# MCU.net
KiCad netlist of a schematic drawn in Altium Designer
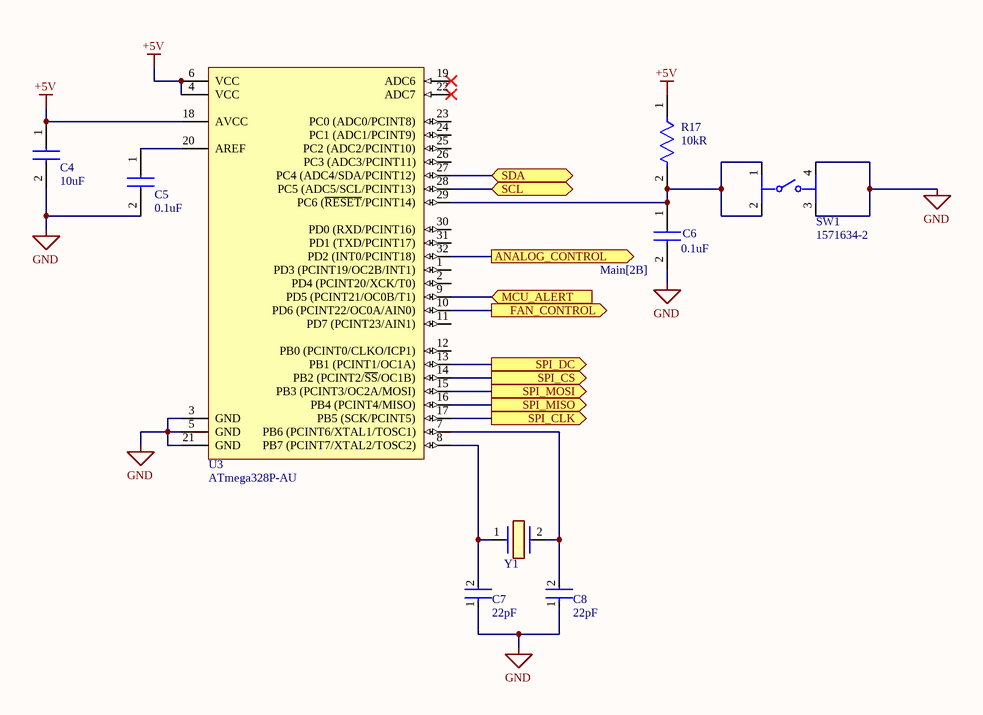
[diagram p0: MCU.SchDoc]

(export (version "E")
  (design (tool "Eeschema 10.0.6"))
  (components
    (comp (ref "C4")
      (value "CL31A106MAHNNNE")
      (footprint "SamacSys:CAPC3216X180N")
      (description "CAP CER 10UF 25V X5R 1206 CL31A106MAHNNNE")
      (fields (field (name "MOUSER PART NUMBER") "187-CL31A106MAHNNNE") (field (name "CAPACITANCE") "10uF"))
      (libsource (lib "SamacSys") (part "CL31A106MAHNNNE"))
    )
    (comp (ref "C5")
      (value "CL31B104KBCNNNC")
      (footprint "SamacSys:CAPC3216X100N")
      (description "CAP CER 0.1UF 50V X7R 1206")
      (fields (field (name "MOUSER PART NUMBER") "187-CL31B104KBCNNNC") (field (name "CAPACITANCE") "0.1uF"))
      (libsource (lib "SamacSys") (part "CL31B104KBCNNNC"))
    )
    (comp (ref "C6")
      (value "CL31B104KBCNNNC")
      (footprint "SamacSys:CAPC3216X100N")
      (description "CAP CER 0.1UF 50V X7R 1206")
      (fields (field (name "MOUSER PART NUMBER") "187-CL31B104KBCNNNC") (field (name "CAPACITANCE") "0.1uF"))
      (libsource (lib "SamacSys") (part "CL31B104KBCNNNC"))
    )
    (comp (ref "C7")
      (value "CL31C220JBCNNNC")
      (footprint "FP-CL31-IPC_A")
      (description "Cap Ceramic 22pF 50V C0G ±5% SMD 1206 +125°C Embossed T/R")
      (fields
        (field (name "VOLTAGE") "50V")
        (field (name "TOLERANCE") "5%")
        (field (name "CAPACITANCE") "22pF")
      )
      (libsource (lib "Altium Content Vault") (part "b4654b650e69147ec39a6b967a45e02"))
    )
    (comp (ref "C8")
      (value "CL31C220JBCNNNC")
      (footprint "FP-CL31-IPC_A")
      (description "Cap Ceramic 22pF 50V C0G ±5% SMD 1206 +125°C Embossed T/R")
      (fields
        (field (name "VOLTAGE") "50V")
        (field (name "TOLERANCE") "5%")
        (field (name "CAPACITANCE") "22pF")
      )
      (libsource (lib "Altium Content Vault") (part "b4654b650e69147ec39a6b967a45e02"))
    )
    (comp (ref "R17")
      (value "RMCF1206FT10K0")
      (footprint "FP-RMCF1206-IPC_B")
      (description "10kΩ ±1% 0.25W 1206 Thick Film Chip Resistor AEC-Q200 compliant RMCF1206FT10K0")
      (fields (field (name "RESISTANCE") "10kR") (field (name "TOLERANCE") "1%"))
      (libsource (lib "Altium Content Vault") (part "1029c3af85768c4190bb7ad29bc67b5"))
    )
    (comp (ref "SW1")
      (value "1571634-2")
      (footprint "FP-1571634-2-MFG")
      (description "SWITCH TACTILE SPST-NO 0.05A 24V")
      (libsource (lib "Altium Content Vault") (part "512b1658425e80dc09bd29e095ee4d3"))
    )
    (comp (ref "U3")
      (value "ATmega328P-AU")
      (footprint "32A_M")
      (libsource (lib "Altium Content Vault") (part "MC-8B-ATM48-SQ32"))
    )
    (comp (ref "Y1")
      (value "ECS-160-20-3X-TR")
      (footprint "SamacSys:ECS160203XTR")
      (description "Crystal or Oscillator")
      (fields (field (name "MOUSER PART NUMBER") "520-160-20-3XT"))
      (libsource (lib "SamacSys") (part "ECS-160-20-3X-TR"))
    )
  )
  (nets
    (net (code "1") (name "+5V") (class "Default")
      (node (ref "C4") (pin "1") (pinfunction "1_1") (pintype "passive"))
      (node (ref "R17") (pin "1") (pinfunction "1_1") (pintype "passive"))
      (node (ref "U3") (pin "18") (pinfunction "AVCC_18") (pintype "power_in"))
      (node (ref "U3") (pin "4") (pinfunction "VCC_4") (pintype "power_in"))
      (node (ref "U3") (pin "6") (pinfunction "VCC_6") (pintype "power_in"))
    )
    (net (code "2") (name "/ANALOG_CONTROL") (class "Default")
      (node (ref "U3") (pin "32") (pinfunction "PD2_(INT0/PCINT18)_32") (pintype "bidirectional"))
    )
    (net (code "3") (name "/FAN_CONTROL") (class "Default")
      (node (ref "U3") (pin "10") (pinfunction "PD6_(PCINT22/OC0A/AIN0)_10") (pintype "bidirectional"))
    )
    (net (code "4") (name "/MCU_ALERT") (class "Default")
      (node (ref "U3") (pin "9") (pinfunction "PD5_(PCINT21/OC0B/T1)_9") (pintype "bidirectional"))
    )
    (net (code "5") (name "/SCL") (class "Default")
      (node (ref "U3") (pin "28") (pinfunction "PC5_(ADC5/SCL/PCINT13)_28") (pintype "bidirectional"))
    )
    (net (code "6") (name "/SDA") (class "Default")
      (node (ref "U3") (pin "27") (pinfunction "PC4_(ADC4/SDA/PCINT12)_27") (pintype "bidirectional"))
    )
    (net (code "7") (name "/SPI_CLK") (class "Default")
      (node (ref "U3") (pin "17") (pinfunction "PB5_(SCK/PCINT5)_17") (pintype "bidirectional"))
    )
    (net (code "8") (name "/SPI_CS") (class "Default")
      (node (ref "U3") (pin "14") (pinfunction "PB2_(PCINT2/~{SS}/OC1B)_14") (pintype "bidirectional"))
    )
    (net (code "9") (name "/SPI_DC") (class "Default")
      (node (ref "U3") (pin "13") (pinfunction "PB1_(PCINT1/OC1A)_13") (pintype "bidirectional"))
    )
    (net (code "10") (name "/SPI_MISO") (class "Default")
      (node (ref "U3") (pin "16") (pinfunction "PB4_(PCINT4/MISO)_16") (pintype "bidirectional"))
    )
    (net (code "11") (name "/SPI_MOSI") (class "Default")
      (node (ref "U3") (pin "15") (pinfunction "PB3_(PCINT3/OC2A/MOSI)_15") (pintype "bidirectional"))
    )
    (net (code "12") (name "GND") (class "Default")
      (node (ref "C4") (pin "2") (pinfunction "2_2") (pintype "passive"))
      (node (ref "C5") (pin "2") (pinfunction "2_2") (pintype "passive"))
      (node (ref "C6") (pin "2") (pinfunction "2_2") (pintype "passive"))
      (node (ref "C7") (pin "1") (pinfunction "1_1") (pintype "passive"))
      (node (ref "C8") (pin "1") (pinfunction "1_1") (pintype "passive"))
      (node (ref "SW1") (pin "3") (pinfunction "3_3") (pintype "passive"))
      (node (ref "SW1") (pin "4") (pinfunction "4_4") (pintype "passive"))
      (node (ref "U3") (pin "21") (pinfunction "GND_21") (pintype "power_in"))
      (node (ref "U3") (pin "3") (pinfunction "GND_3") (pintype "power_in"))
      (node (ref "U3") (pin "5") (pinfunction "GND_5") (pintype "power_in"))
    )
    (net (code "13") (name "Net-(U3-AREF)") (class "Default")
      (node (ref "C5") (pin "1") (pinfunction "1_1") (pintype "passive"))
      (node (ref "U3") (pin "20") (pinfunction "AREF_20") (pintype "passive"))
    )
    (net (code "14") (name "Net-(U3-PB6_(PCINT6{slash}XTAL1{slash}TOSC1))") (class "Default")
      (node (ref "C8") (pin "2") (pinfunction "2_2") (pintype "passive"))
      (node (ref "U3") (pin "7") (pinfunction "PB6_(PCINT6/XTAL1/TOSC1)_7") (pintype "bidirectional"))
      (node (ref "Y1") (pin "2") (pinfunction "X2_2") (pintype "passive"))
    )
    (net (code "15") (name "Net-(U3-PB7_(PCINT7{slash}XTAL2{slash}TOSC2))") (class "Default")
      (node (ref "C7") (pin "2") (pinfunction "2_2") (pintype "passive"))
      (node (ref "U3") (pin "8") (pinfunction "PB7_(PCINT7/XTAL2/TOSC2)_8") (pintype "bidirectional"))
      (node (ref "Y1") (pin "1") (pinfunction "X1_1") (pintype "passive"))
    )
    (net (code "16") (name "Net-(U3-PC6_(~{RESET}{slash}PCINT14))") (class "Default")
      (node (ref "C6") (pin "1") (pinfunction "1_1") (pintype "passive"))
      (node (ref "R17") (pin "2") (pinfunction "2_2") (pintype "passive"))
      (node (ref "SW1") (pin "1") (pinfunction "1_1") (pintype "passive"))
      (node (ref "SW1") (pin "2") (pinfunction "2_2") (pintype "passive"))
      (node (ref "U3") (pin "29") (pinfunction "PC6_(~{RESET}/PCINT14)_29") (pintype "bidirectional"))
    )
    (net (code "17") (name "unconnected-(U3-ADC6-Pad19)") (class "Default")
      (node (ref "U3") (pin "19") (pinfunction "ADC6_19") (pintype "input+no_connect"))
    )
    (net (code "18") (name "unconnected-(U3-ADC7-Pad22)") (class "Default")
      (node (ref "U3") (pin "22") (pinfunction "ADC7_22") (pintype "input+no_connect"))
    )
    (net (code "19") (name "unconnected-(U3-PB0_(PCINT0{slash}CLKO{slash}ICP1)-Pad12)") (class "Default")
      (node (ref "U3") (pin "12") (pinfunction "PB0_(PCINT0/CLKO/ICP1)_12") (pintype "bidirectional"))
    )
    (net (code "20") (name "unconnected-(U3-PC0_(ADC0{slash}PCINT8)-Pad23)") (class "Default")
      (node (ref "U3") (pin "23") (pinfunction "PC0_(ADC0/PCINT8)_23") (pintype "bidirectional"))
    )
    (net (code "21") (name "unconnected-(U3-PC1_(ADC1{slash}PCINT9)-Pad24)") (class "Default")
      (node (ref "U3") (pin "24") (pinfunction "PC1_(ADC1/PCINT9)_24") (pintype "bidirectional"))
    )
    (net (code "22") (name "unconnected-(U3-PC2_(ADC2{slash}PCINT10)-Pad25)") (class "Default")
      (node (ref "U3") (pin "25") (pinfunction "PC2_(ADC2/PCINT10)_25") (pintype "bidirectional"))
    )
    (net (code "23") (name "unconnected-(U3-PC3_(ADC3{slash}PCINT11)-Pad26)") (class "Default")
      (node (ref "U3") (pin "26") (pinfunction "PC3_(ADC3/PCINT11)_26") (pintype "bidirectional"))
    )
    (net (code "24") (name "unconnected-(U3-PD0_(RXD{slash}PCINT16)-Pad30)") (class "Default")
      (node (ref "U3") (pin "30") (pinfunction "PD0_(RXD/PCINT16)_30") (pintype "bidirectional"))
    )
    (net (code "25") (name "unconnected-(U3-PD1_(TXD{slash}PCINT17)-Pad31)") (class "Default")
      (node (ref "U3") (pin "31") (pinfunction "PD1_(TXD/PCINT17)_31") (pintype "bidirectional"))
    )
    (net (code "26") (name "unconnected-(U3-PD3_(PCINT19{slash}OC2B{slash}INT1)-Pad1)") (class "Default")
      (node (ref "U3") (pin "1") (pinfunction "PD3_(PCINT19/OC2B/INT1)_1") (pintype "bidirectional"))
    )
    (net (code "27") (name "unconnected-(U3-PD4_(PCINT20{slash}XCK{slash}T0)-Pad2)") (class "Default")
      (node (ref "U3") (pin "2") (pinfunction "PD4_(PCINT20/XCK/T0)_2") (pintype "bidirectional"))
    )
    (net (code "28") (name "unconnected-(U3-PD7_(PCINT23{slash}AIN1)-Pad11)") (class "Default")
      (node (ref "U3") (pin "11") (pinfunction "PD7_(PCINT23/AIN1)_11") (pintype "bidirectional"))
    )
  )
)
